# meteo-slave.net
KiCad netlist of a schematic drawn in EAGLE
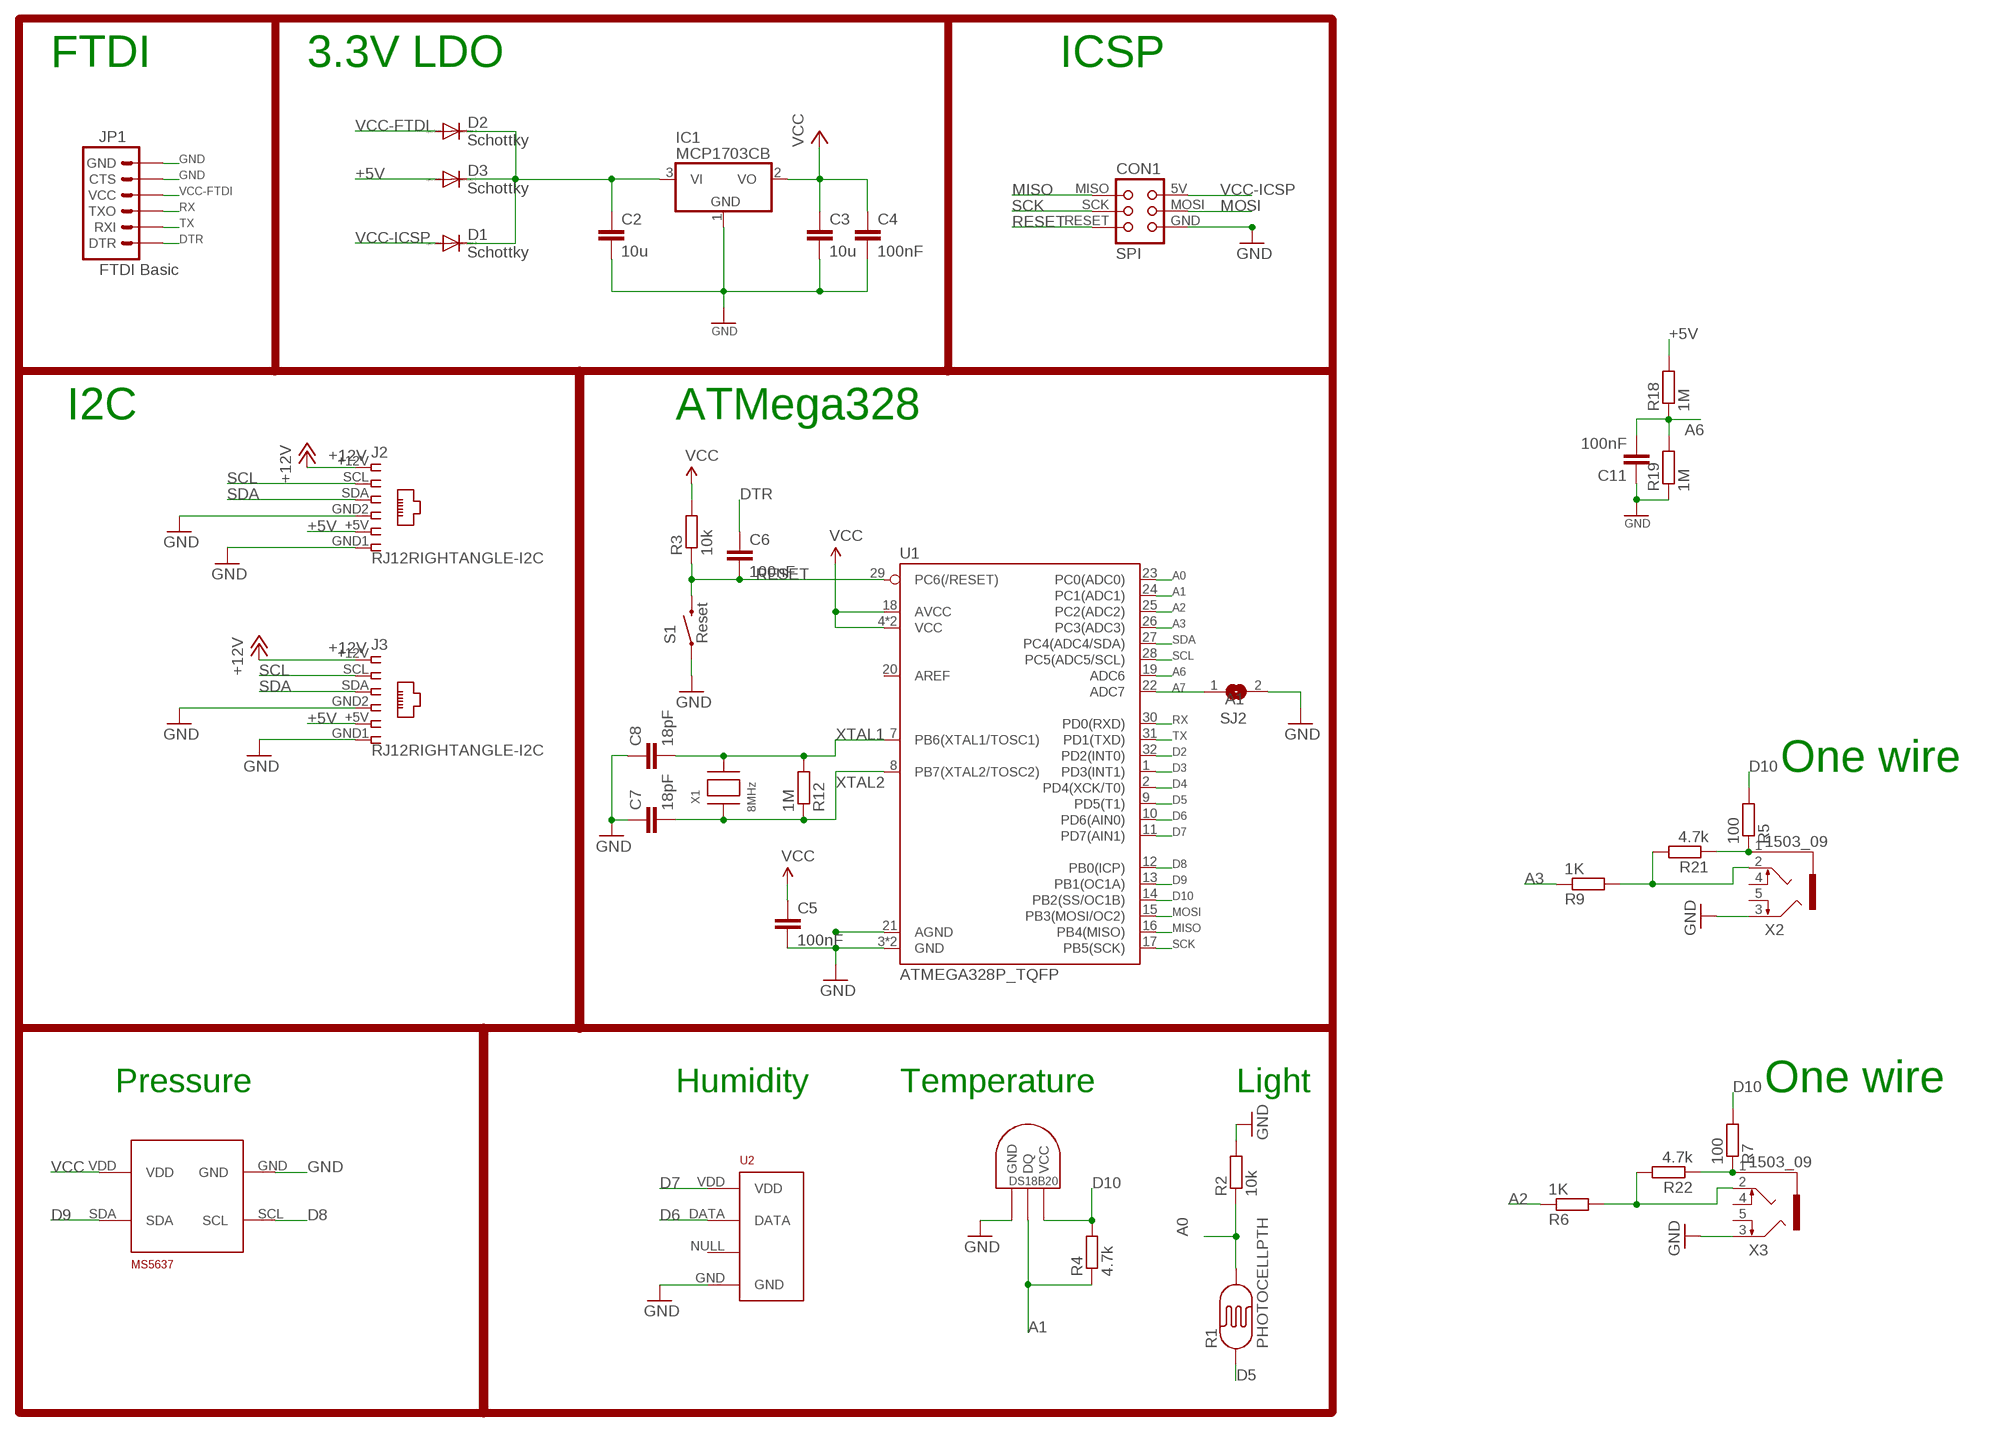
[diagram p0: schematic, sheet 1]

(export (version "E")
  (design (tool "Eeschema 10.0.6"))
  (components
    (comp (ref "C2")
      (value "10u")
      (footprint "eagle-import:C0805K")
      (fields (field (name "MPN") "77-VJ1206V106ZXQTBC"))
      (libsource (lib "eagle-import") (part "C-EUC0805K"))
    )
    (comp (ref "C3")
      (value "10u")
      (footprint "eagle-import:C0805K")
      (fields (field (name "MPN") "77-VJ1206V106ZXQTBC"))
      (libsource (lib "eagle-import") (part "C-EUC0805K"))
    )
    (comp (ref "C4")
      (value "100nF")
      (footprint "eagle-import:C0805K")
      (fields (field (name "MPN") "80-C1206C104K5R"))
      (libsource (lib "eagle-import") (part "C-EUC0805K"))
    )
    (comp (ref "C5")
      (value "100nF")
      (footprint "eagle-import:C0805K")
      (fields (field (name "MPN") "80-C1206C104K5R"))
      (libsource (lib "eagle-import") (part "C-EUC0805K"))
    )
    (comp (ref "C6")
      (value "100nF")
      (footprint "eagle-import:C0805K")
      (fields (field (name "MPN") "80-C1206C104K5R"))
      (libsource (lib "eagle-import") (part "C-EUC0805K"))
    )
    (comp (ref "C7")
      (value "18pF")
      (footprint "eagle-import:C0805K")
      (fields (field (name "MPN") "77-VJ1206A180JXXPBC"))
      (libsource (lib "eagle-import") (part "C-EUC0805K"))
    )
    (comp (ref "C8")
      (value "18pF")
      (footprint "eagle-import:C0805K")
      (fields (field (name "MPN") "77-VJ1206A180JXXPBC"))
      (libsource (lib "eagle-import") (part "C-EUC0805K"))
    )
    (comp (ref "C11")
      (value "100nF")
      (footprint "eagle-import:C0805K")
      (fields (field (name "MPN") "80-C1206C104K5R"))
      (libsource (lib "eagle-import") (part "C-EUC0805K"))
    )
    (comp (ref "CON1")
      (value "SPI")
      (footprint "eagle-import:TC2030-MCP")
      (libsource (lib "eagle-import") (part "TINYISPTAG"))
    )
    (comp (ref "D1")
      (value "Schottky")
      (footprint "eagle-import:SOD123")
      (fields (field (name "MPN") "621-1N5819HW-F"))
      (libsource (lib "eagle-import") (part "MBR0520LT"))
    )
    (comp (ref "D2")
      (value "Schottky")
      (footprint "eagle-import:SOD123")
      (fields (field (name "MPN") "621-1N5819HW-F"))
      (libsource (lib "eagle-import") (part "MBR0520LT"))
    )
    (comp (ref "D3")
      (value "Schottky")
      (footprint "eagle-import:SOD123")
      (fields (field (name "MPN") "621-1N5819HW-F"))
      (libsource (lib "eagle-import") (part "MBR0520LT"))
    )
    (comp (ref "IC1")
      (value "MCP1703CB")
      (footprint "eagle-import:SOT23")
      (libsource (lib "eagle-import") (part "MCP1703CB"))
    )
    (comp (ref "J2")
      (value "RJ12RIGHTANGLE-I2C")
      (footprint "eagle-import:RJ12-RIGHTANGLE-I2C")
      (libsource (lib "eagle-import") (part "RJ12RIGHTANGLE-I2C"))
    )
    (comp (ref "J3")
      (value "RJ12RIGHTANGLE-I2C")
      (footprint "eagle-import:RJ12-RIGHTANGLE-I2C")
      (libsource (lib "eagle-import") (part "RJ12RIGHTANGLE-I2C"))
    )
    (comp (ref "JP1")
      (value "FTDI Basic")
      (footprint "eagle-import:1X06")
      (libsource (lib "eagle-import") (part "ARDUINO_SERIAL_PROGRAMPTH"))
    )
    (comp (ref "R1")
      (value "PHOTOCELLPTH")
      (footprint "eagle-import:PHOTOCELL")
      (libsource (lib "eagle-import") (part "PHOTOCELLPTH"))
    )
    (comp (ref "R2")
      (value "10k")
      (footprint "eagle-import:R0805")
      (libsource (lib "eagle-import") (part "resistor_348_R-EU_R0805"))
    )
    (comp (ref "R3")
      (value "10k")
      (footprint "eagle-import:R0805")
      (libsource (lib "eagle-import") (part "R-EU_R0805"))
    )
    (comp (ref "R4")
      (value "4.7k")
      (footprint "eagle-import:R0805")
      (libsource (lib "eagle-import") (part "resistor_348_R-EU_R0805"))
    )
    (comp (ref "R5")
      (value "100")
      (footprint "eagle-import:R0805")
      (libsource (lib "eagle-import") (part "R-EU_R0805"))
    )
    (comp (ref "R6")
      (value "1K")
      (footprint "eagle-import:R0805")
      (libsource (lib "eagle-import") (part "R-EU_R0805"))
    )
    (comp (ref "R7")
      (value "100")
      (footprint "eagle-import:R0805")
      (libsource (lib "eagle-import") (part "R-EU_R0805"))
    )
    (comp (ref "R9")
      (value "1K")
      (footprint "eagle-import:R0805")
      (libsource (lib "eagle-import") (part "R-EU_R0805"))
    )
    (comp (ref "R12")
      (value "1M")
      (footprint "eagle-import:R0805")
      (libsource (lib "eagle-import") (part "R-EU_R0805"))
    )
    (comp (ref "R18")
      (value "1M")
      (footprint "eagle-import:R0805")
      (libsource (lib "eagle-import") (part "R-EU_R0805"))
    )
    (comp (ref "R19")
      (value "1M")
      (footprint "eagle-import:R0805")
      (libsource (lib "eagle-import") (part "R-EU_R0805"))
    )
    (comp (ref "R21")
      (value "4.7k")
      (footprint "eagle-import:R0805")
      (libsource (lib "eagle-import") (part "resistor_R-EU_R0805"))
    )
    (comp (ref "R22")
      (value "4.7k")
      (footprint "eagle-import:R0805")
      (libsource (lib "eagle-import") (part "resistor_R-EU_R0805"))
    )
    (comp (ref "S1")
      (value "Reset")
      (footprint "eagle-import:TACTILE-SWITCH-SMD-ALT01")
      (libsource (lib "eagle-import") (part "SWITCH-MOMENTARY-2SMD-ALT01"))
    )
    (comp (ref "SJ2") (value "A1") (footprint "eagle-import:SJ") (libsource (lib "eagle-import") (part "SJ")))
    (comp (ref "U$1")
      (value "DS1820TO92")
      (footprint "eagle-import:DS1820")
      (libsource (lib "eagle-import") (part "DS1820TO92"))
    )
    (comp (ref "U$19")
      (value "MS5637WIDE")
      (footprint "eagle-import:MS5637WIDE")
      (libsource (lib "eagle-import") (part "MS5637WIDE"))
    )
    (comp (ref "U1")
      (value "ATMEGA328P_TQFP")
      (footprint "eagle-import:TQFP32-08")
      (libsource (lib "eagle-import") (part "ATMEGA328P_TQFP"))
    )
    (comp (ref "U2")
      (value "RHT03_DHT-22_AM2302")
      (footprint "eagle-import:RHT03_DHT-22")
      (libsource (lib "eagle-import") (part "RHT03_DHT-22_AM2302"))
    )
    (comp (ref "X1")
      (value "8MHz")
      (footprint "eagle-import:NX6035")
      (fields (field (name "MPN") "729-F60800010"))
      (libsource (lib "eagle-import") (part "XTALNX6035"))
    )
    (comp (ref "X2")
      (value "1503_09")
      (footprint "eagle-import:1503_09")
      (libsource (lib "eagle-import") (part "1503_09"))
    )
    (comp (ref "X3")
      (value "1503_09")
      (footprint "eagle-import:1503_09")
      (libsource (lib "eagle-import") (part "1503_09"))
    )
  )
  (nets
    (net (code "1") (name "+5V") (class "Default")
      (node (ref "D3") (pin "A") (pinfunction "A_A") (pintype "passive"))
      (node (ref "J2") (pin "+5V") (pinfunction "5_+5V") (pintype "bidirectional"))
      (node (ref "J3") (pin "+5V") (pinfunction "5_+5V") (pintype "bidirectional"))
      (node (ref "R18") (pin "2") (pinfunction "2_2") (pintype "passive"))
    )
    (net (code "2") (name "+12V") (class "Default")
      (node (ref "J2") (pin "+12V") (pinfunction "1_+12V") (pintype "bidirectional"))
      (node (ref "J3") (pin "+12V") (pinfunction "1_+12V") (pintype "bidirectional"))
    )
    (net (code "3") (name "A0") (class "Default")
      (node (ref "R1") (pin "2") (pinfunction "P$2_2") (pintype "bidirectional"))
      (node (ref "R2") (pin "1") (pinfunction "1_1") (pintype "passive"))
      (node (ref "U1") (pin "23") (pinfunction "PC0(ADC0)_23") (pintype "bidirectional"))
    )
    (net (code "4") (name "A1") (class "Default")
      (node (ref "R4") (pin "1") (pinfunction "1_1") (pintype "passive"))
      (node (ref "U$1") (pin "DQ") (pinfunction "DQ_DQ") (pintype "bidirectional"))
      (node (ref "U1") (pin "24") (pinfunction "PC1(ADC1)_24") (pintype "bidirectional"))
    )
    (net (code "5") (name "A2") (class "Default")
      (node (ref "R6") (pin "1") (pinfunction "1_1") (pintype "passive"))
      (node (ref "U1") (pin "25") (pinfunction "PC2(ADC2)_25") (pintype "bidirectional"))
    )
    (net (code "6") (name "A3") (class "Default")
      (node (ref "R9") (pin "1") (pinfunction "1_1") (pintype "passive"))
      (node (ref "U1") (pin "26") (pinfunction "PC3(ADC3)_26") (pintype "bidirectional"))
    )
    (net (code "7") (name "A6") (class "Default")
      (node (ref "C11") (pin "2") (pinfunction "2_2") (pintype "passive"))
      (node (ref "R18") (pin "1") (pinfunction "1_1") (pintype "passive"))
      (node (ref "R19") (pin "2") (pinfunction "2_2") (pintype "passive"))
      (node (ref "U1") (pin "19") (pinfunction "ADC6_19") (pintype "bidirectional"))
    )
    (net (code "8") (name "A7") (class "Default")
      (node (ref "SJ2") (pin "1") (pinfunction "1_1") (pintype "passive"))
      (node (ref "U1") (pin "22") (pinfunction "ADC7_22") (pintype "bidirectional"))
    )
    (net (code "9") (name "D2") (class "Default")
      (node (ref "U1") (pin "32") (pinfunction "PD2(INT0)_32") (pintype "bidirectional"))
    )
    (net (code "10") (name "D3") (class "Default")
      (node (ref "U1") (pin "1") (pinfunction "PD3(INT1)_1") (pintype "bidirectional"))
    )
    (net (code "11") (name "D4") (class "Default")
      (node (ref "U1") (pin "2") (pinfunction "PD4(XCK/T0)_2") (pintype "bidirectional"))
    )
    (net (code "12") (name "D5") (class "Default")
      (node (ref "R1") (pin "1") (pinfunction "P$1_1") (pintype "bidirectional"))
      (node (ref "U1") (pin "9") (pinfunction "PD5(T1)_9") (pintype "bidirectional"))
    )
    (net (code "13") (name "D6") (class "Default")
      (node (ref "U1") (pin "10") (pinfunction "PD6(AIN0)_10") (pintype "bidirectional"))
      (node (ref "U2") (pin "DATA") (pinfunction "DATA_DATA") (pintype "bidirectional"))
    )
    (net (code "14") (name "D7") (class "Default")
      (node (ref "U1") (pin "11") (pinfunction "PD7(AIN1)_11") (pintype "bidirectional"))
      (node (ref "U2") (pin "VDD") (pinfunction "VDD_VDD") (pintype "power_in"))
    )
    (net (code "15") (name "D8") (class "Default")
      (node (ref "U$19") (pin "SCL") (pinfunction "SCL_SCL") (pintype "bidirectional"))
      (node (ref "U1") (pin "12") (pinfunction "PB0(ICP)_12") (pintype "bidirectional"))
    )
    (net (code "16") (name "D9") (class "Default")
      (node (ref "U$19") (pin "SDA") (pinfunction "SDA_SDA") (pintype "bidirectional"))
      (node (ref "U1") (pin "13") (pinfunction "PB1(OC1A)_13") (pintype "bidirectional"))
    )
    (net (code "17") (name "D10") (class "Default")
      (node (ref "R4") (pin "2") (pinfunction "2_2") (pintype "passive"))
      (node (ref "R5") (pin "2") (pinfunction "2_2") (pintype "passive"))
      (node (ref "R7") (pin "2") (pinfunction "2_2") (pintype "passive"))
      (node (ref "U$1") (pin "VDD") (pinfunction "VCC_VDD") (pintype "power_in"))
      (node (ref "U1") (pin "14") (pinfunction "PB2(SS/OC1B)_14") (pintype "bidirectional"))
    )
    (net (code "18") (name "DTR") (class "Default")
      (node (ref "C6") (pin "1") (pinfunction "1_1") (pintype "passive"))
      (node (ref "JP1") (pin "1") (pinfunction "DTR_1") (pintype "passive"))
    )
    (net (code "19") (name "GND") (class "Default")
      (node (ref "C11") (pin "1") (pinfunction "1_1") (pintype "passive"))
      (node (ref "C2") (pin "2") (pinfunction "2_2") (pintype "passive"))
      (node (ref "C3") (pin "2") (pinfunction "2_2") (pintype "passive"))
      (node (ref "C4") (pin "2") (pinfunction "2_2") (pintype "passive"))
      (node (ref "C5") (pin "2") (pinfunction "2_2") (pintype "passive"))
      (node (ref "C7") (pin "1") (pinfunction "1_1") (pintype "passive"))
      (node (ref "C8") (pin "1") (pinfunction "1_1") (pintype "passive"))
      (node (ref "CON1") (pin "GND") (pinfunction "GND_GND") (pintype "passive"))
      (node (ref "IC1") (pin "1") (pinfunction "GND_1") (pintype "passive"))
      (node (ref "J2") (pin "GND1") (pinfunction "6_GND1") (pintype "bidirectional"))
      (node (ref "J2") (pin "GND2") (pinfunction "4_GND2") (pintype "bidirectional"))
      (node (ref "J3") (pin "GND1") (pinfunction "6_GND1") (pintype "bidirectional"))
      (node (ref "J3") (pin "GND2") (pinfunction "4_GND2") (pintype "bidirectional"))
      (node (ref "JP1") (pin "5") (pinfunction "CTS_5") (pintype "passive"))
      (node (ref "JP1") (pin "6") (pinfunction "GND_6") (pintype "passive"))
      (node (ref "R19") (pin "1") (pinfunction "1_1") (pintype "passive"))
      (node (ref "R2") (pin "2") (pinfunction "2_2") (pintype "passive"))
      (node (ref "S1") (pin "1") (pinfunction "1_1") (pintype "passive"))
      (node (ref "S1") (pin "2") (pinfunction "1_2") (pintype "passive"))
      (node (ref "SJ2") (pin "2") (pinfunction "2_2") (pintype "passive"))
      (node (ref "U$1") (pin "GND") (pinfunction "GND_GND") (pintype "power_in"))
      (node (ref "U$19") (pin "GND") (pinfunction "GND_GND") (pintype "bidirectional"))
      (node (ref "U1") (pin "21") (pinfunction "AGND_21") (pintype "bidirectional"))
      (node (ref "U1") (pin "3") (pinfunction "GND_3") (pintype "bidirectional"))
      (node (ref "U1") (pin "5") (pinfunction "GND_5") (pintype "bidirectional"))
      (node (ref "U2") (pin "GND") (pinfunction "GND_GND") (pintype "power_in"))
      (node (ref "X2") (pin "3") (pinfunction "3_3") (pintype "passive"))
      (node (ref "X3") (pin "3") (pinfunction "3_3") (pintype "passive"))
    )
    (net (code "20") (name "MISO") (class "Default")
      (node (ref "CON1") (pin "MISO") (pinfunction "MISO_MISO") (pintype "passive"))
      (node (ref "U1") (pin "16") (pinfunction "PB4(MISO)_16") (pintype "bidirectional"))
    )
    (net (code "21") (name "MOSI") (class "Default")
      (node (ref "CON1") (pin "MOSI") (pinfunction "MOSI_MOSI") (pintype "passive"))
      (node (ref "U1") (pin "15") (pinfunction "PB3(MOSI/OC2)_15") (pintype "bidirectional"))
    )
    (net (code "22") (name "Net-(IC1-VI)") (class "Default")
      (node (ref "C2") (pin "1") (pinfunction "1_1") (pintype "passive"))
      (node (ref "D1") (pin "C") (pinfunction "C_C") (pintype "passive"))
      (node (ref "D2") (pin "C") (pinfunction "C_C") (pintype "passive"))
      (node (ref "D3") (pin "C") (pinfunction "C_C") (pintype "passive"))
      (node (ref "IC1") (pin "3") (pinfunction "VI_3") (pintype "input"))
    )
    (net (code "23") (name "Net-(R21-Pad1)") (class "Default")
      (node (ref "R21") (pin "1") (pinfunction "1_1") (pintype "passive"))
      (node (ref "R5") (pin "1") (pinfunction "1_1") (pintype "passive"))
      (node (ref "X2") (pin "1") (pinfunction "1_1") (pintype "passive"))
    )
    (net (code "24") (name "Net-(R21-Pad2)") (class "Default")
      (node (ref "R21") (pin "2") (pinfunction "2_2") (pintype "passive"))
      (node (ref "R9") (pin "2") (pinfunction "2_2") (pintype "passive"))
      (node (ref "X2") (pin "2") (pinfunction "2_2") (pintype "passive"))
    )
    (net (code "25") (name "Net-(R22-Pad1)") (class "Default")
      (node (ref "R22") (pin "1") (pinfunction "1_1") (pintype "passive"))
      (node (ref "R7") (pin "1") (pinfunction "1_1") (pintype "passive"))
      (node (ref "X3") (pin "1") (pinfunction "1_1") (pintype "passive"))
    )
    (net (code "26") (name "Net-(R22-Pad2)") (class "Default")
      (node (ref "R22") (pin "2") (pinfunction "2_2") (pintype "passive"))
      (node (ref "R6") (pin "2") (pinfunction "2_2") (pintype "passive"))
      (node (ref "X3") (pin "2") (pinfunction "2_2") (pintype "passive"))
    )
    (net (code "27") (name "RESET") (class "Default")
      (node (ref "C6") (pin "2") (pinfunction "2_2") (pintype "passive"))
      (node (ref "CON1") (pin "RESET") (pinfunction "RESET_RESET") (pintype "passive"))
      (node (ref "R3") (pin "1") (pinfunction "1_1") (pintype "passive"))
      (node (ref "S1") (pin "3") (pinfunction "2_3") (pintype "passive"))
      (node (ref "S1") (pin "4") (pinfunction "2_4") (pintype "passive"))
      (node (ref "U1") (pin "29") (pinfunction "PC6(/RESET)_29") (pintype "bidirectional"))
    )
    (net (code "28") (name "RX") (class "Default")
      (node (ref "JP1") (pin "3") (pinfunction "TXO_3") (pintype "passive"))
      (node (ref "U1") (pin "30") (pinfunction "PD0(RXD)_30") (pintype "bidirectional"))
    )
    (net (code "29") (name "SCK") (class "Default")
      (node (ref "CON1") (pin "SCK") (pinfunction "SCK_SCK") (pintype "passive"))
      (node (ref "U1") (pin "17") (pinfunction "PB5(SCK)_17") (pintype "bidirectional"))
    )
    (net (code "30") (name "SCL") (class "Default")
      (node (ref "J2") (pin "SCL") (pinfunction "2_SCL") (pintype "bidirectional"))
      (node (ref "J3") (pin "SCL") (pinfunction "2_SCL") (pintype "bidirectional"))
      (node (ref "U1") (pin "28") (pinfunction "PC5(ADC5/SCL)_28") (pintype "bidirectional"))
    )
    (net (code "31") (name "SDA") (class "Default")
      (node (ref "J2") (pin "SDA") (pinfunction "3_SDA") (pintype "bidirectional"))
      (node (ref "J3") (pin "SDA") (pinfunction "3_SDA") (pintype "bidirectional"))
      (node (ref "U1") (pin "27") (pinfunction "PC4(ADC4/SDA)_27") (pintype "bidirectional"))
    )
    (net (code "32") (name "TX") (class "Default")
      (node (ref "JP1") (pin "2") (pinfunction "RXI_2") (pintype "passive"))
      (node (ref "U1") (pin "31") (pinfunction "PD1(TXD)_31") (pintype "bidirectional"))
    )
    (net (code "33") (name "VCC") (class "Default")
      (node (ref "C3") (pin "1") (pinfunction "1_1") (pintype "passive"))
      (node (ref "C4") (pin "1") (pinfunction "1_1") (pintype "passive"))
      (node (ref "C5") (pin "1") (pinfunction "1_1") (pintype "passive"))
      (node (ref "IC1") (pin "2") (pinfunction "VO_2") (pintype "passive"))
      (node (ref "R3") (pin "2") (pinfunction "2_2") (pintype "passive"))
      (node (ref "U$19") (pin "VDD") (pinfunction "VDD_VDD") (pintype "bidirectional"))
      (node (ref "U1") (pin "18") (pinfunction "AVCC_18") (pintype "bidirectional"))
      (node (ref "U1") (pin "4") (pinfunction "VCC_4") (pintype "bidirectional"))
      (node (ref "U1") (pin "6") (pinfunction "VCC_6") (pintype "bidirectional"))
    )
    (net (code "34") (name "VCC-FTDI") (class "Default")
      (node (ref "D2") (pin "A") (pinfunction "A_A") (pintype "passive"))
      (node (ref "JP1") (pin "4") (pinfunction "VCC_4") (pintype "passive"))
    )
    (net (code "35") (name "VCC-ICSP") (class "Default")
      (node (ref "CON1") (pin "5V") (pinfunction "VCC_5V") (pintype "passive"))
      (node (ref "D1") (pin "A") (pinfunction "A_A") (pintype "passive"))
    )
    (net (code "36") (name "XTAL1") (class "Default")
      (node (ref "C8") (pin "2") (pinfunction "2_2") (pintype "passive"))
      (node (ref "R12") (pin "2") (pinfunction "2_2") (pintype "passive"))
      (node (ref "U1") (pin "7") (pinfunction "PB6(XTAL1/TOSC1)_7") (pintype "bidirectional"))
      (node (ref "X1") (pin "P$2") (pinfunction "P$2_P$2") (pintype "bidirectional"))
    )
    (net (code "37") (name "XTAL2") (class "Default")
      (node (ref "C7") (pin "2") (pinfunction "2_2") (pintype "passive"))
      (node (ref "R12") (pin "1") (pinfunction "1_1") (pintype "passive"))
      (node (ref "U1") (pin "8") (pinfunction "PB7(XTAL2/TOSC2)_8") (pintype "bidirectional"))
      (node (ref "X1") (pin "P$1") (pinfunction "P$1_P$1") (pintype "bidirectional"))
    )
    (net (code "38") (name "unconnected-(U1-AREF-Pad20)") (class "Default")
      (node (ref "U1") (pin "20") (pinfunction "AREF_20") (pintype "bidirectional"))
    )
    (net (code "39") (name "unconnected-(U2-PadNULL)") (class "Default")
      (node (ref "U2") (pin "NULL") (pinfunction "NULL_NULL") (pintype "no_connect"))
    )
    (net (code "40") (name "unconnected-(X2-Pad4)") (class "Default")
      (node (ref "X2") (pin "4") (pinfunction "4_4") (pintype "passive"))
    )
    (net (code "41") (name "unconnected-(X2-Pad5)") (class "Default")
      (node (ref "X2") (pin "5") (pinfunction "5_5") (pintype "passive"))
    )
    (net (code "42") (name "unconnected-(X3-Pad4)") (class "Default")
      (node (ref "X3") (pin "4") (pinfunction "4_4") (pintype "passive"))
    )
    (net (code "43") (name "unconnected-(X3-Pad5)") (class "Default")
      (node (ref "X3") (pin "5") (pinfunction "5_5") (pintype "passive"))
    )
  )
)
